# untitled.net
KiCad netlist of a schematic drawn in EAGLE
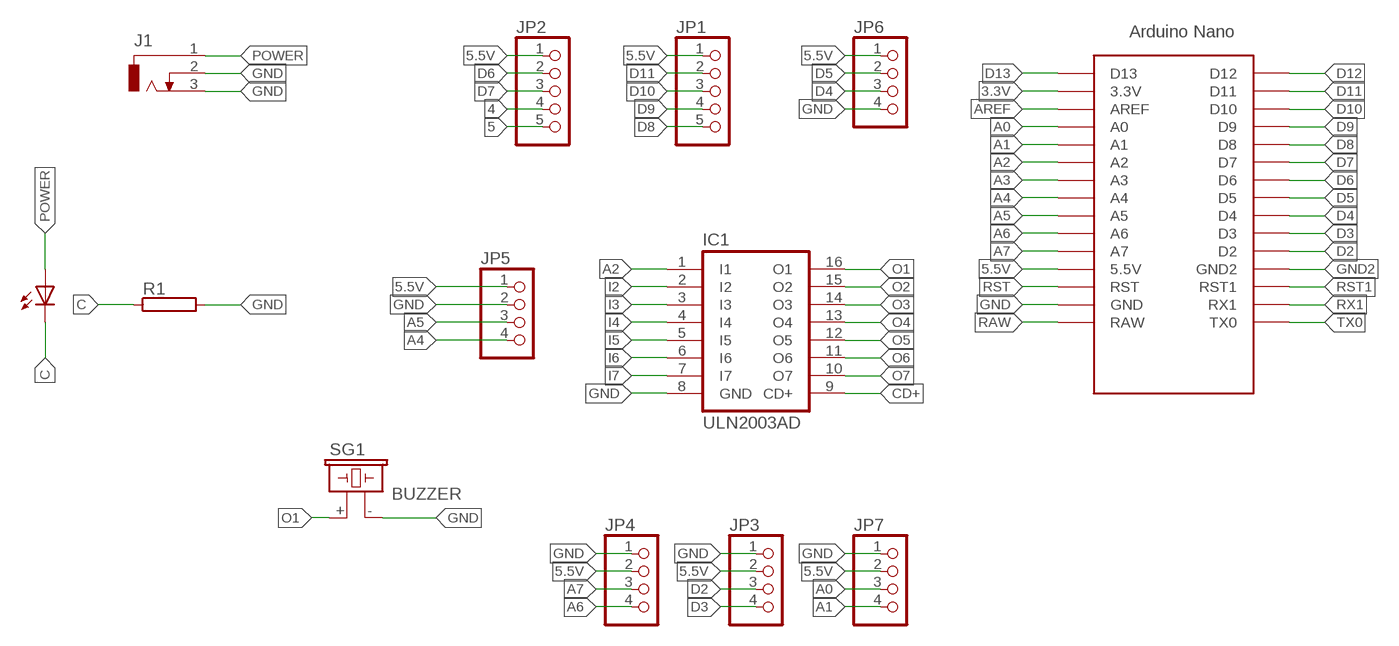
[diagram p0: schematic, sheet 1]

(export (version "E")
  (design (tool "Eeschema 10.0.6"))
  (components
    (comp (ref "IC1")
      (value "ULN2003AD")
      (footprint "eagle-import:SO16")
      (libsource (lib "eagle-import") (part "ULN2003AD"))
    )
    (comp (ref "J1")
      (value "CON_JACK")
      (footprint "eagle-import:DCJ0303")
      (libsource (lib "eagle-import") (part "CON_JACK"))
    )
    (comp (ref "JP1")
      (value "PINHD-1X5")
      (footprint "eagle-import:1X05")
      (libsource (lib "eagle-import") (part "PINHD-1X5"))
    )
    (comp (ref "JP2")
      (value "PINHD-1X5")
      (footprint "eagle-import:1X05")
      (libsource (lib "eagle-import") (part "PINHD-1X5"))
    )
    (comp (ref "JP3")
      (value "PINHD-1X4")
      (footprint "eagle-import:1X04")
      (libsource (lib "eagle-import") (part "PINHD-1X4"))
    )
    (comp (ref "JP4")
      (value "PINHD-1X4")
      (footprint "eagle-import:1X04")
      (libsource (lib "eagle-import") (part "PINHD-1X4"))
    )
    (comp (ref "JP5")
      (value "PINHD-1X4")
      (footprint "eagle-import:1X04")
      (libsource (lib "eagle-import") (part "PINHD-1X4"))
    )
    (comp (ref "JP6")
      (value "PINHD-1X4")
      (footprint "eagle-import:1X04")
      (libsource (lib "eagle-import") (part "PINHD-1X4"))
    )
    (comp (ref "JP7")
      (value "PINHD-1X4")
      (footprint "eagle-import:1X04")
      (libsource (lib "eagle-import") (part "PINHD-1X4"))
    )
    (comp (ref "R1")
      (value "RMG100-H")
      (footprint "eagle-import:TO-247-2H")
      (libsource (lib "eagle-import") (part "RMG100-H"))
    )
    (comp (ref "SG1")
      (value "BUZZER")
      (footprint "eagle-import:F_CM12P")
      (libsource (lib "eagle-import") (part "BUZZER"))
    )
    (comp (ref "U$1")
      (value "ARDUINO_NANO")
      (footprint "eagle-import:NANO")
      (libsource (lib "eagle-import") (part "ARDUINO_NANO"))
    )
    (comp (ref "U$2")
      (value "LED5MM")
      (footprint "eagle-import:LED5MM")
      (libsource (lib "eagle-import") (part "LED5MM"))
    )
  )
  (nets
    (net (code "1") (name "3.3V") (class "Default")
      (node (ref "U$1") (pin "3.3V") (pinfunction "3.3V_3.3V") (pintype "bidirectional"))
    )
    (net (code "2") (name "4") (class "Default")
      (node (ref "JP2") (pin "4") (pinfunction "4_4") (pintype "passive"))
    )
    (net (code "3") (name "5") (class "Default")
      (node (ref "JP2") (pin "5") (pinfunction "5_5") (pintype "passive"))
    )
    (net (code "4") (name "5.5V") (class "Default")
      (node (ref "JP1") (pin "1") (pinfunction "1_1") (pintype "passive"))
      (node (ref "JP2") (pin "1") (pinfunction "1_1") (pintype "passive"))
      (node (ref "JP3") (pin "2") (pinfunction "2_2") (pintype "passive"))
      (node (ref "JP4") (pin "2") (pinfunction "2_2") (pintype "passive"))
      (node (ref "JP5") (pin "1") (pinfunction "1_1") (pintype "passive"))
      (node (ref "JP6") (pin "1") (pinfunction "1_1") (pintype "passive"))
      (node (ref "JP7") (pin "2") (pinfunction "2_2") (pintype "passive"))
      (node (ref "U$1") (pin "5V") (pinfunction "5.5V_5V") (pintype "bidirectional"))
    )
    (net (code "5") (name "A0") (class "Default")
      (node (ref "JP7") (pin "3") (pinfunction "3_3") (pintype "passive"))
      (node (ref "U$1") (pin "A0") (pinfunction "A0_A0") (pintype "bidirectional"))
    )
    (net (code "6") (name "A1") (class "Default")
      (node (ref "JP7") (pin "4") (pinfunction "4_4") (pintype "passive"))
      (node (ref "U$1") (pin "A1") (pinfunction "A1_A1") (pintype "bidirectional"))
    )
    (net (code "7") (name "A2") (class "Default")
      (node (ref "IC1") (pin "1") (pinfunction "I1_1") (pintype "input"))
      (node (ref "U$1") (pin "A2") (pinfunction "A2_A2") (pintype "bidirectional"))
    )
    (net (code "8") (name "A3") (class "Default")
      (node (ref "U$1") (pin "A3") (pinfunction "A3_A3") (pintype "bidirectional"))
    )
    (net (code "9") (name "A4") (class "Default")
      (node (ref "JP5") (pin "4") (pinfunction "4_4") (pintype "passive"))
      (node (ref "U$1") (pin "A4") (pinfunction "A4_A4") (pintype "bidirectional"))
    )
    (net (code "10") (name "A5") (class "Default")
      (node (ref "JP5") (pin "3") (pinfunction "3_3") (pintype "passive"))
      (node (ref "U$1") (pin "A5") (pinfunction "A5_A5") (pintype "bidirectional"))
    )
    (net (code "11") (name "A6") (class "Default")
      (node (ref "JP4") (pin "4") (pinfunction "4_4") (pintype "passive"))
      (node (ref "U$1") (pin "A6") (pinfunction "A6_A6") (pintype "bidirectional"))
    )
    (net (code "12") (name "A7") (class "Default")
      (node (ref "JP4") (pin "3") (pinfunction "3_3") (pintype "passive"))
      (node (ref "U$1") (pin "A7") (pinfunction "A7_A7") (pintype "bidirectional"))
    )
    (net (code "13") (name "AREF") (class "Default")
      (node (ref "U$1") (pin "AREF") (pinfunction "AREF_AREF") (pintype "bidirectional"))
    )
    (net (code "14") (name "C") (class "Default")
      (node (ref "R1") (pin "1") (pinfunction "1_1") (pintype "passive"))
      (node (ref "U$2") (pin "K") (pinfunction "C_K") (pintype "passive"))
    )
    (net (code "15") (name "CD+") (class "Default")
      (node (ref "IC1") (pin "9") (pinfunction "CD+_9") (pintype "passive"))
    )
    (net (code "16") (name "D2") (class "Default")
      (node (ref "JP3") (pin "3") (pinfunction "3_3") (pintype "passive"))
      (node (ref "U$1") (pin "D2") (pinfunction "D2_D2") (pintype "bidirectional"))
    )
    (net (code "17") (name "D3") (class "Default")
      (node (ref "JP3") (pin "4") (pinfunction "4_4") (pintype "passive"))
      (node (ref "U$1") (pin "D3") (pinfunction "D3_D3") (pintype "bidirectional"))
    )
    (net (code "18") (name "D4") (class "Default")
      (node (ref "JP6") (pin "3") (pinfunction "3_3") (pintype "passive"))
      (node (ref "U$1") (pin "D4") (pinfunction "D4_D4") (pintype "bidirectional"))
    )
    (net (code "19") (name "D5") (class "Default")
      (node (ref "JP6") (pin "2") (pinfunction "2_2") (pintype "passive"))
      (node (ref "U$1") (pin "D5") (pinfunction "D5_D5") (pintype "bidirectional"))
    )
    (net (code "20") (name "D6") (class "Default")
      (node (ref "JP2") (pin "2") (pinfunction "2_2") (pintype "passive"))
      (node (ref "U$1") (pin "D6") (pinfunction "D6_D6") (pintype "bidirectional"))
    )
    (net (code "21") (name "D7") (class "Default")
      (node (ref "JP2") (pin "3") (pinfunction "3_3") (pintype "passive"))
      (node (ref "U$1") (pin "D7") (pinfunction "D7_D7") (pintype "bidirectional"))
    )
    (net (code "22") (name "D8") (class "Default")
      (node (ref "JP1") (pin "5") (pinfunction "5_5") (pintype "passive"))
      (node (ref "U$1") (pin "D8") (pinfunction "D8_D8") (pintype "bidirectional"))
    )
    (net (code "23") (name "D9") (class "Default")
      (node (ref "JP1") (pin "4") (pinfunction "4_4") (pintype "passive"))
      (node (ref "U$1") (pin "D9") (pinfunction "D9_D9") (pintype "bidirectional"))
    )
    (net (code "24") (name "D10") (class "Default")
      (node (ref "JP1") (pin "3") (pinfunction "3_3") (pintype "passive"))
      (node (ref "U$1") (pin "D10") (pinfunction "D10_D10") (pintype "bidirectional"))
    )
    (net (code "25") (name "D11") (class "Default")
      (node (ref "JP1") (pin "2") (pinfunction "2_2") (pintype "passive"))
      (node (ref "U$1") (pin "D11") (pinfunction "D11_D11") (pintype "bidirectional"))
    )
    (net (code "26") (name "D12") (class "Default")
      (node (ref "U$1") (pin "D12") (pinfunction "D12_D12") (pintype "bidirectional"))
    )
    (net (code "27") (name "D13") (class "Default")
      (node (ref "U$1") (pin "D13") (pinfunction "D13_D13") (pintype "bidirectional"))
    )
    (net (code "28") (name "GND") (class "Default")
      (node (ref "IC1") (pin "8") (pinfunction "GND_8") (pintype "power_in"))
      (node (ref "J1") (pin "2") (pinfunction "2_2") (pintype "passive"))
      (node (ref "J1") (pin "3") (pinfunction "3_3") (pintype "passive"))
      (node (ref "JP3") (pin "1") (pinfunction "1_1") (pintype "passive"))
      (node (ref "JP4") (pin "1") (pinfunction "1_1") (pintype "passive"))
      (node (ref "JP5") (pin "2") (pinfunction "2_2") (pintype "passive"))
      (node (ref "JP6") (pin "4") (pinfunction "4_4") (pintype "passive"))
      (node (ref "JP7") (pin "1") (pinfunction "1_1") (pintype "passive"))
      (node (ref "R1") (pin "2") (pinfunction "2_2") (pintype "passive"))
      (node (ref "SG1") (pin "-") (pinfunction "2_-") (pintype "passive"))
      (node (ref "U$1") (pin "GND") (pinfunction "GND_GND") (pintype "bidirectional"))
    )
    (net (code "29") (name "GND2") (class "Default")
      (node (ref "U$1") (pin "GND1") (pinfunction "GND2_GND1") (pintype "bidirectional"))
    )
    (net (code "30") (name "I2") (class "Default")
      (node (ref "IC1") (pin "2") (pinfunction "I2_2") (pintype "input"))
    )
    (net (code "31") (name "I3") (class "Default")
      (node (ref "IC1") (pin "3") (pinfunction "I3_3") (pintype "input"))
    )
    (net (code "32") (name "I4") (class "Default")
      (node (ref "IC1") (pin "4") (pinfunction "I4_4") (pintype "input"))
    )
    (net (code "33") (name "I5") (class "Default")
      (node (ref "IC1") (pin "5") (pinfunction "I5_5") (pintype "input"))
    )
    (net (code "34") (name "I6") (class "Default")
      (node (ref "IC1") (pin "6") (pinfunction "I6_6") (pintype "input"))
    )
    (net (code "35") (name "I7") (class "Default")
      (node (ref "IC1") (pin "7") (pinfunction "I7_7") (pintype "input"))
    )
    (net (code "36") (name "O1") (class "Default")
      (node (ref "IC1") (pin "16") (pinfunction "O1_16") (pintype "open_collector"))
      (node (ref "SG1") (pin "+") (pinfunction "1_+") (pintype "passive"))
    )
    (net (code "37") (name "O2") (class "Default")
      (node (ref "IC1") (pin "15") (pinfunction "O2_15") (pintype "open_collector"))
    )
    (net (code "38") (name "O3") (class "Default")
      (node (ref "IC1") (pin "14") (pinfunction "O3_14") (pintype "open_collector"))
    )
    (net (code "39") (name "O4") (class "Default")
      (node (ref "IC1") (pin "13") (pinfunction "O4_13") (pintype "open_collector"))
    )
    (net (code "40") (name "O5") (class "Default")
      (node (ref "IC1") (pin "12") (pinfunction "O5_12") (pintype "open_collector"))
    )
    (net (code "41") (name "O6") (class "Default")
      (node (ref "IC1") (pin "11") (pinfunction "O6_11") (pintype "open_collector"))
    )
    (net (code "42") (name "O7") (class "Default")
      (node (ref "IC1") (pin "10") (pinfunction "O7_10") (pintype "open_collector"))
    )
    (net (code "43") (name "POWER") (class "Default")
      (node (ref "J1") (pin "1") (pinfunction "1_1") (pintype "passive"))
      (node (ref "U$2") (pin "A") (pinfunction "A_A") (pintype "passive"))
    )
    (net (code "44") (name "RAW") (class "Default")
      (node (ref "U$1") (pin "RAW") (pinfunction "RAW_RAW") (pintype "bidirectional"))
    )
    (net (code "45") (name "RST") (class "Default")
      (node (ref "U$1") (pin "RST") (pinfunction "RST_RST") (pintype "bidirectional"))
    )
    (net (code "46") (name "RST1") (class "Default")
      (node (ref "U$1") (pin "RST1") (pinfunction "RST1_RST1") (pintype "bidirectional"))
    )
    (net (code "47") (name "RX1") (class "Default")
      (node (ref "U$1") (pin "RX1") (pinfunction "RX1_RX1") (pintype "bidirectional"))
    )
    (net (code "48") (name "TX0") (class "Default")
      (node (ref "U$1") (pin "TX0") (pinfunction "TX0_TX0") (pintype "bidirectional"))
    )
  )
)
